# chipjabbersimplev1.net
KiCad netlist of a schematic drawn in Altium Designer
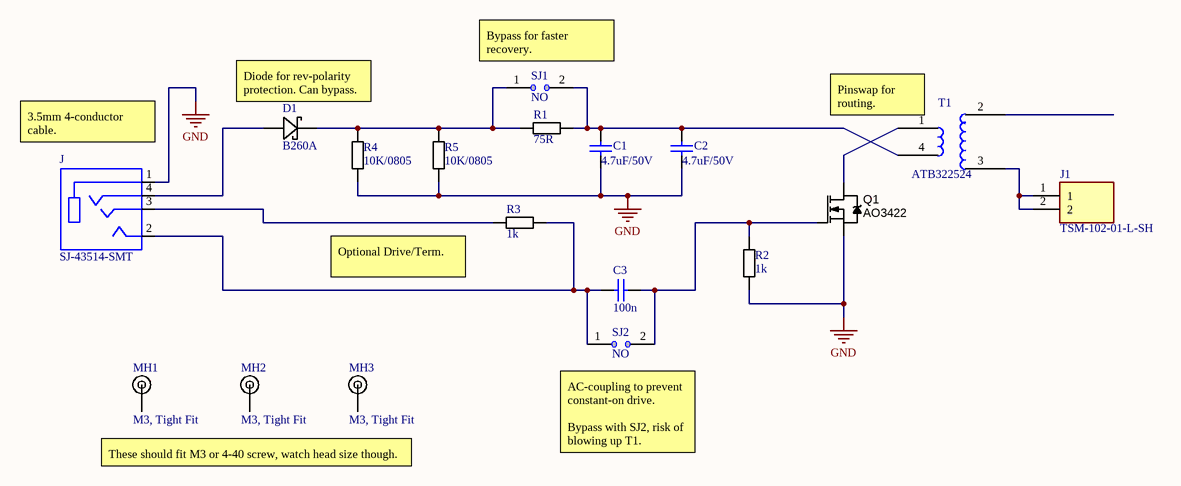
[diagram p0: chipjabbersimplev1.SchDoc]

(export (version "E")
  (design (tool "Eeschema 10.0.6"))
  (components
    (comp (ref "C1")
      (value "4.7uF/50V")
      (footprint "CAPC0805_M")
      (description "4u7, 50V, 0805, Ceramic")
      (fields (field (name "PART NUMBER") "CCHIP-4u7-0805-50V") (field (name "TOLERANCE") "10%"))
      (libsource (lib "NewAE_AltiumLib") (part "CAP"))
    )
    (comp (ref "C2")
      (value "4.7uF/50V")
      (footprint "CAPC0805_M")
      (description "4u7, 50V, 0805, Ceramic")
      (fields (field (name "PART NUMBER") "CCHIP-4u7-0805-50V") (field (name "TOLERANCE") "10%"))
      (libsource (lib "NewAE_AltiumLib") (part "CAP"))
    )
    (comp (ref "C3")
      (value "100n")
      (footprint "CAPC0603_M")
      (description "100n, 0603")
      (fields (field (name "PART NUMBER") "CCHIP-100n-0603"))
      (libsource (lib "NewAE_AltiumLib") (part "CAP"))
    )
    (comp (ref "D1")
      (value "B260A")
      (footprint "DIOM4326X23N")
      (description "DIODE SCHOTTKY 60V 2A SMA")
      (fields (field (name "PART NUMBER") "DIODE_SCHOTTKY_2A"))
      (libsource (lib "NewAE_AltiumLib") (part "DIODE_SCHOTTKY"))
    )
    (comp (ref "J")
      (value "SJ-43514-SMT")
      (footprint "CUI_SJ-43514-SMT")
      (description "4 conductor TRS, 3.5mm")
      (fields (field (name "MF") "CUI Devices"))
      (libsource (lib "NewAE_AltiumLib") (part "SJ-43514-SMT"))
    )
    (comp (ref "J1")
      (value "TSM-102-01-L-SH")
      (footprint "SamacSys:TSM-102-YY-ZZZ-SH")
      (description "Connector")
      (fields (field (name "MOUSER PART NUMBER") "200-TSM10201LSH"))
      (libsource (lib "*") (part "TSM-102-01-L-SH"))
    )
    (comp (ref "MH1")
      (value "M3, Tight Fit")
      (footprint "MOUNT_M3_TIGHT")
      (description "Machine screw M3 Mounting Hole")
      (fields (field (name "PART NUMBER") "MOUNT_M3_TIGHT"))
      (libsource (lib "NewAE_AltiumLib") (part "Mounting_Hole"))
    )
    (comp (ref "MH2")
      (value "M3, Tight Fit")
      (footprint "MOUNT_M3_TIGHT")
      (description "Machine screw M3 Mounting Hole")
      (fields (field (name "PART NUMBER") "MOUNT_M3_TIGHT"))
      (libsource (lib "NewAE_AltiumLib") (part "Mounting_Hole"))
    )
    (comp (ref "MH3")
      (value "M3, Tight Fit")
      (footprint "MOUNT_M3_TIGHT")
      (description "Machine screw M3 Mounting Hole")
      (fields (field (name "PART NUMBER") "MOUNT_M3_TIGHT"))
      (libsource (lib "NewAE_AltiumLib") (part "Mounting_Hole"))
    )
    (comp (ref "Q1")
      (value "AO3422")
      (footprint "SOT95P245X110-3M")
      (description "MOSFET N-CH 30V 2.2A SOT23-3")
      (fields (field (name "PART NUMBER") "DMN3200U-7"))
      (libsource (lib "NewAE_AltiumLib") (part "MOSFET_N_GSD"))
    )
    (comp (ref "R1")
      (value "75R")
      (footprint "RESC2012X70N")
      (description "75R res, 0805, 1%, 1/8W")
      (fields (field (name "PART NUMBER") "RCHIP-75R-0805") (field (name "TOLERANCE") "1%"))
      (libsource (lib "") (part "RES-EU_1"))
    )
    (comp (ref "R2")
      (value "1k")
      (footprint "RESC1608X55N")
      (description "1k res, 0603, 1%, 1/10W")
      (fields (field (name "PART NUMBER") "RCHIP-1K-0603") (field (name "TOLERANCE") "1%"))
      (libsource (lib "NewAE_AltiumLib") (part "RES-EU"))
    )
    (comp (ref "R3")
      (value "1k")
      (footprint "RESC1608X55N")
      (description "1k res, 0603, 1%, 1/10W")
      (fields (field (name "PART NUMBER") "RCHIP-1K-0603") (field (name "TOLERANCE") "1%"))
      (libsource (lib "") (part "RES-EU_1"))
    )
    (comp (ref "R4")
      (value "10K/0805")
      (footprint "RESC2012X70N")
      (description "75R res, 0805, 1%, 1/8W")
      (fields (field (name "PART NUMBER") "RCHIP-75R-0805") (field (name "TOLERANCE") "1%"))
      (libsource (lib "NewAE_AltiumLib") (part "RES-EU"))
    )
    (comp (ref "R5")
      (value "10K/0805")
      (footprint "RESC2012X70N")
      (description "75R res, 0805, 1%, 1/8W")
      (fields (field (name "PART NUMBER") "RCHIP-75R-0805") (field (name "TOLERANCE") "1%"))
      (libsource (lib "NewAE_AltiumLib") (part "RES-EU"))
    )
    (comp (ref "SJ1")
      (value "NO")
      (footprint "SJ_2S_NO")
      (description "Solder Jumper, NO")
      (fields (field (name "PART NUMBER") "SJ_2S_NO"))
      (libsource (lib "NewAE_AltiumLib") (part "SJ_2S_NO"))
    )
    (comp (ref "SJ2")
      (value "NO")
      (footprint "SJ_2S_NO")
      (description "Solder Jumper, NO")
      (fields (field (name "PART NUMBER") "SJ_2S_NO"))
      (libsource (lib "NewAE_AltiumLib") (part "SJ_2S_NO"))
    )
    (comp (ref "T1")
      (value "ATB322524")
      (footprint "ATB322524_CHUNKY")
      (description "HV Transformer 1:10, Small")
      (fields (field (name "PART NUMBER") "ATB322524_PROTO"))
      (libsource (lib "NewAE_AltiumLib") (part "xformer_2_2_hv"))
    )
  )
  (nets
    (net (code "1") (name "GND") (class "Default")
      (node (ref "C1") (pin "2") (pinfunction "2_2") (pintype "passive"))
      (node (ref "C2") (pin "2") (pinfunction "2_2") (pintype "passive"))
      (node (ref "J") (pin "1") (pinfunction "SLEEVE_1") (pintype "passive"))
      (node (ref "Q1") (pin "2") (pinfunction "S_2") (pintype "passive"))
      (node (ref "R2") (pin "2") (pinfunction "2_2") (pintype "passive"))
      (node (ref "R4") (pin "2") (pinfunction "2_2") (pintype "passive"))
      (node (ref "R5") (pin "2") (pinfunction "2_2") (pintype "passive"))
    )
    (net (code "2") (name "Net-(C1-Pad1)") (class "Default")
      (node (ref "C1") (pin "1") (pinfunction "1_1") (pintype "passive"))
      (node (ref "C2") (pin "1") (pinfunction "1_1") (pintype "passive"))
      (node (ref "R1") (pin "2") (pinfunction "2_2") (pintype "passive"))
      (node (ref "SJ1") (pin "2") (pinfunction "2_2") (pintype "passive"))
      (node (ref "T1") (pin "4") (pinfunction "4_4") (pintype "passive"))
    )
    (net (code "3") (name "Net-(D1-PadK)") (class "Default")
      (node (ref "D1") (pin "K") (pinfunction "K_K") (pintype "passive"))
      (node (ref "R1") (pin "1") (pinfunction "1_1") (pintype "passive"))
      (node (ref "R4") (pin "1") (pinfunction "1_1") (pintype "passive"))
      (node (ref "R5") (pin "1") (pinfunction "1_1") (pintype "passive"))
      (node (ref "SJ1") (pin "1") (pinfunction "1_1") (pintype "passive"))
    )
    (net (code "4") (name "Net-(J-RING1)") (class "Default")
      (node (ref "J") (pin "3") (pinfunction "RING1_3") (pintype "passive"))
      (node (ref "R3") (pin "1") (pinfunction "1_1") (pintype "passive"))
    )
    (net (code "5") (name "Net-(J-RING2)") (class "Default")
      (node (ref "D1") (pin "A") (pinfunction "A_A") (pintype "passive"))
      (node (ref "J") (pin "4") (pinfunction "RING2_4") (pintype "passive"))
    )
    (net (code "6") (name "Net-(J-TIP)") (class "Default")
      (node (ref "C3") (pin "1") (pinfunction "1_1") (pintype "passive"))
      (node (ref "J") (pin "2") (pinfunction "TIP_2") (pintype "passive"))
      (node (ref "R3") (pin "2") (pinfunction "2_2") (pintype "passive"))
      (node (ref "SJ2") (pin "1") (pinfunction "1_1") (pintype "passive"))
    )
    (net (code "7") (name "Net-(J1-Pad1)") (class "Default")
      (node (ref "J1") (pin "1") (pinfunction "1_1") (pintype "passive"))
      (node (ref "J1") (pin "2") (pinfunction "2_2") (pintype "passive"))
      (node (ref "T1") (pin "3") (pinfunction "3_3") (pintype "passive"))
    )
    (net (code "8") (name "Net-(Q1-D)") (class "Default")
      (node (ref "Q1") (pin "3") (pinfunction "D_3") (pintype "passive"))
      (node (ref "T1") (pin "1") (pinfunction "1_1") (pintype "passive"))
    )
    (net (code "9") (name "Net-(Q1-G)") (class "Default")
      (node (ref "C3") (pin "2") (pinfunction "2_2") (pintype "passive"))
      (node (ref "Q1") (pin "1") (pinfunction "G_1") (pintype "passive"))
      (node (ref "R2") (pin "1") (pinfunction "1_1") (pintype "passive"))
      (node (ref "SJ2") (pin "2") (pinfunction "2_2") (pintype "passive"))
    )
    (net (code "10") (name "unconnected-(MH1-Pad1)") (class "Default")
      (node (ref "MH1") (pin "1") (pinfunction "1_1") (pintype "passive"))
    )
    (net (code "11") (name "unconnected-(MH2-Pad1)") (class "Default")
      (node (ref "MH2") (pin "1") (pinfunction "1_1") (pintype "passive"))
    )
    (net (code "12") (name "unconnected-(MH3-Pad1)") (class "Default")
      (node (ref "MH3") (pin "1") (pinfunction "1_1") (pintype "passive"))
    )
    (net (code "13") (name "unconnected-(T1-Pad2)") (class "Default")
      (node (ref "T1") (pin "2") (pinfunction "2_2") (pintype "passive"))
    )
  )
)
